# Connectors.net
KiCad netlist of a schematic drawn in Altium Designer
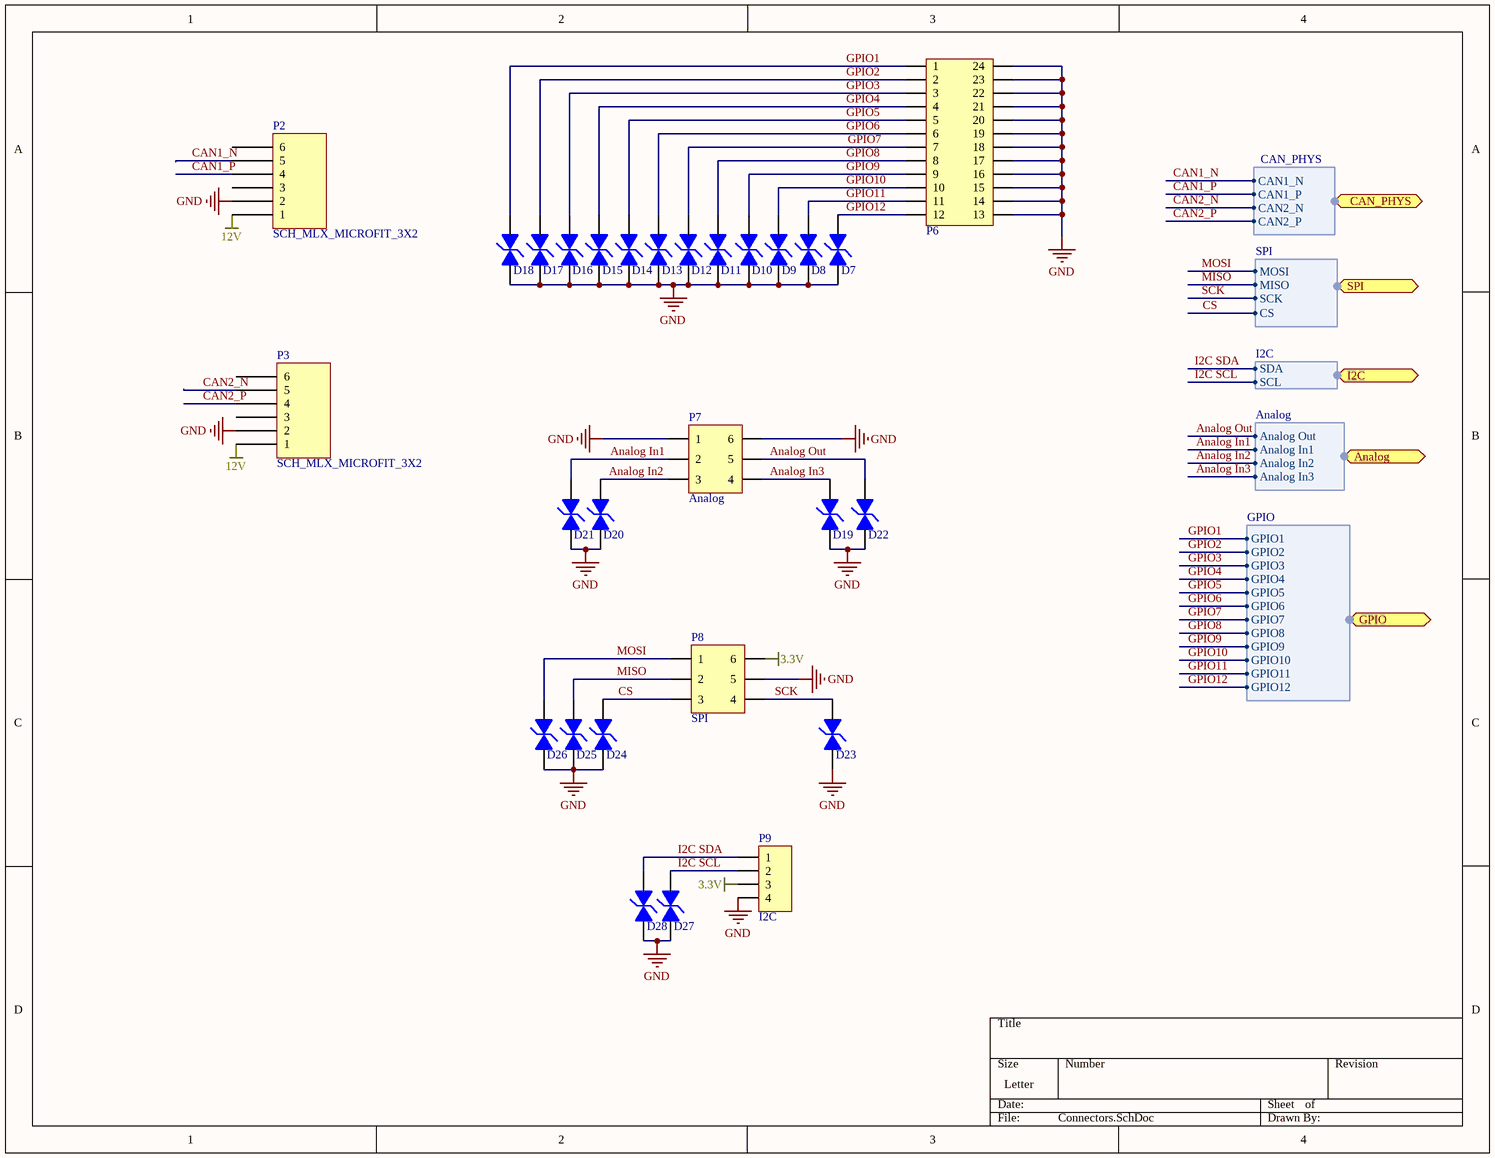
[diagram p0: Connectors.SchDoc]

(export (version "E")
  (design (tool "Eeschema 10.0.6"))
  (components
    (comp (ref "D7")
      (value "TVS Diode")
      (footprint "TVS Diode")
      (fields (field (name "MANUFACTURER") "Bourns"))
      (libsource (lib "TVS Diode") (part "TVS Diode"))
    )
    (comp (ref "D8")
      (value "TVS Diode")
      (footprint "TVS Diode")
      (fields (field (name "MANUFACTURER") "Bourns"))
      (libsource (lib "TVS Diode") (part "TVS Diode"))
    )
    (comp (ref "D9")
      (value "TVS Diode")
      (footprint "TVS Diode")
      (fields (field (name "MANUFACTURER") "Bourns"))
      (libsource (lib "TVS Diode") (part "TVS Diode"))
    )
    (comp (ref "D10")
      (value "TVS Diode")
      (footprint "TVS Diode")
      (fields (field (name "MANUFACTURER") "Bourns"))
      (libsource (lib "TVS Diode") (part "TVS Diode"))
    )
    (comp (ref "D11")
      (value "TVS Diode")
      (footprint "TVS Diode")
      (fields (field (name "MANUFACTURER") "Bourns"))
      (libsource (lib "TVS Diode") (part "TVS Diode"))
    )
    (comp (ref "D12")
      (value "TVS Diode")
      (footprint "TVS Diode")
      (fields (field (name "MANUFACTURER") "Bourns"))
      (libsource (lib "TVS Diode") (part "TVS Diode"))
    )
    (comp (ref "D13")
      (value "TVS Diode")
      (footprint "TVS Diode")
      (fields (field (name "MANUFACTURER") "Bourns"))
      (libsource (lib "TVS Diode") (part "TVS Diode"))
    )
    (comp (ref "D14")
      (value "TVS Diode")
      (footprint "TVS Diode")
      (fields (field (name "MANUFACTURER") "Bourns"))
      (libsource (lib "TVS Diode") (part "TVS Diode"))
    )
    (comp (ref "D15")
      (value "TVS Diode")
      (footprint "TVS Diode")
      (fields (field (name "MANUFACTURER") "Bourns"))
      (libsource (lib "TVS Diode") (part "TVS Diode"))
    )
    (comp (ref "D16")
      (value "TVS Diode")
      (footprint "TVS Diode")
      (fields (field (name "MANUFACTURER") "Bourns"))
      (libsource (lib "TVS Diode") (part "TVS Diode"))
    )
    (comp (ref "D17")
      (value "TVS Diode")
      (footprint "TVS Diode")
      (fields (field (name "MANUFACTURER") "Bourns"))
      (libsource (lib "TVS Diode") (part "TVS Diode"))
    )
    (comp (ref "D18")
      (value "TVS Diode")
      (footprint "TVS Diode")
      (fields (field (name "MANUFACTURER") "Bourns"))
      (libsource (lib "TVS Diode") (part "TVS Diode"))
    )
    (comp (ref "D19")
      (value "TVS Diode")
      (footprint "TVS Diode")
      (fields (field (name "MANUFACTURER") "Bourns"))
      (libsource (lib "TVS Diode") (part "TVS Diode"))
    )
    (comp (ref "D20")
      (value "TVS Diode")
      (footprint "TVS Diode")
      (fields (field (name "MANUFACTURER") "Bourns"))
      (libsource (lib "TVS Diode") (part "TVS Diode"))
    )
    (comp (ref "D21")
      (value "TVS Diode")
      (footprint "TVS Diode")
      (fields (field (name "MANUFACTURER") "Bourns"))
      (libsource (lib "TVS Diode") (part "TVS Diode"))
    )
    (comp (ref "D22")
      (value "TVS Diode")
      (footprint "TVS Diode")
      (fields (field (name "MANUFACTURER") "Bourns"))
      (libsource (lib "TVS Diode") (part "TVS Diode"))
    )
    (comp (ref "D23")
      (value "TVS Diode")
      (footprint "TVS Diode")
      (fields (field (name "MANUFACTURER") "Bourns"))
      (libsource (lib "TVS Diode") (part "TVS Diode"))
    )
    (comp (ref "D24")
      (value "TVS Diode")
      (footprint "TVS Diode")
      (fields (field (name "MANUFACTURER") "Bourns"))
      (libsource (lib "TVS Diode") (part "TVS Diode"))
    )
    (comp (ref "D25")
      (value "TVS Diode")
      (footprint "TVS Diode")
      (fields (field (name "MANUFACTURER") "Bourns"))
      (libsource (lib "TVS Diode") (part "TVS Diode"))
    )
    (comp (ref "D26")
      (value "TVS Diode")
      (footprint "TVS Diode")
      (fields (field (name "MANUFACTURER") "Bourns"))
      (libsource (lib "TVS Diode") (part "TVS Diode"))
    )
    (comp (ref "D27")
      (value "TVS Diode")
      (footprint "TVS Diode")
      (fields (field (name "MANUFACTURER") "Bourns"))
      (libsource (lib "TVS Diode") (part "TVS Diode"))
    )
    (comp (ref "D28")
      (value "TVS Diode")
      (footprint "TVS Diode")
      (fields (field (name "MANUFACTURER") "Bourns"))
      (libsource (lib "TVS Diode") (part "TVS Diode"))
    )
    (comp (ref "P2")
      (value "SCH_MLX_MICROFIT_3X2")
      (footprint "Molex Microfit 3.0 3x2:PCB_MLX_MICROFIT_3X2")
      (libsource (lib "Molex Microfit 3.0 3x2") (part "SCH_MLX_MICROFIT_3X2"))
    )
    (comp (ref "P3")
      (value "SCH_MLX_MICROFIT_3X2")
      (footprint "Molex Microfit 3.0 3x2:PCB_MLX_MICROFIT_3X2")
      (libsource (lib "Molex Microfit 3.0 3x2") (part "SCH_MLX_MICROFIT_3X2"))
    )
    (comp (ref "P6")
      (value "24-Pin Vertical Header")
      (footprint "24-Pin Vertical Header")
      (fields (field (name "MANUFACTURER") "Sullins"))
      (libsource (lib "24 Pin 100 mil Vertical Header - Through Hole") (part "24-Pin Vertical Header"))
    )
    (comp (ref "P7")
      (value "Analog")
      (footprint "6-Pin Vertical Header")
      (fields (field (name "MANUFACTURER") "Sullins"))
      (libsource (lib "6 Pin 100 mil Vertical Header - Through Hole") (part "6-Pin Vertical Header"))
    )
    (comp (ref "P8")
      (value "SPI")
      (footprint "6-Pin Vertical Header")
      (fields (field (name "MANUFACTURER") "Sullins"))
      (libsource (lib "6 Pin 100 mil Vertical Header - Through Hole") (part "6-Pin Vertical Header"))
    )
    (comp (ref "P9")
      (value "I2C")
      (footprint "4-Pin Vertical Header")
      (fields (field (name "MANUFACTURER") "Sullins"))
      (libsource (lib "4 Pin 100 mil Vertical Header - Through Hole") (part "4-Pin Vertical Header"))
    )
  )
  (nets
    (net (code "6") (name "/Analog In1") (class "Default")
      (node (ref "D21") (pin "1") (pintype "passive"))
      (node (ref "P7") (pin "2") (pinfunction "2_2") (pintype "passive"))
    )
    (net (code "7") (name "/Analog In2") (class "Default")
      (node (ref "D20") (pin "1") (pintype "passive"))
      (node (ref "P7") (pin "3") (pinfunction "3_3") (pintype "passive"))
    )
    (net (code "8") (name "/Analog In3") (class "Default")
      (node (ref "D19") (pin "1") (pintype "passive"))
      (node (ref "P7") (pin "4") (pinfunction "4_4") (pintype "passive"))
    )
    (net (code "9") (name "/Analog Out") (class "Default")
      (node (ref "D22") (pin "1") (pintype "passive"))
      (node (ref "P7") (pin "5") (pinfunction "5_5") (pintype "passive"))
    )
    (net (code "10") (name "/CAN1_N") (class "Default")
      (node (ref "P2") (pin "5") (pinfunction "5_5") (pintype "passive"))
    )
    (net (code "11") (name "/CAN1_P") (class "Default")
      (node (ref "P2") (pin "4") (pinfunction "4_4") (pintype "passive"))
    )
    (net (code "12") (name "/CAN2_N") (class "Default")
      (node (ref "P3") (pin "5") (pinfunction "5_5") (pintype "passive"))
    )
    (net (code "13") (name "/CAN2_P") (class "Default")
      (node (ref "P3") (pin "4") (pinfunction "4_4") (pintype "passive"))
    )
    (net (code "14") (name "/CS") (class "Default")
      (node (ref "D24") (pin "1") (pintype "passive"))
      (node (ref "P8") (pin "3") (pinfunction "3_3") (pintype "passive"))
    )
    (net (code "15") (name "/GPIO1") (class "Default")
      (node (ref "D18") (pin "1") (pintype "passive"))
      (node (ref "P6") (pin "1") (pinfunction "1_1") (pintype "passive"))
    )
    (net (code "16") (name "/GPIO2") (class "Default")
      (node (ref "D17") (pin "1") (pintype "passive"))
      (node (ref "P6") (pin "2") (pinfunction "2_2") (pintype "passive"))
    )
    (net (code "17") (name "/GPIO3") (class "Default")
      (node (ref "D16") (pin "1") (pintype "passive"))
      (node (ref "P6") (pin "3") (pinfunction "3_3") (pintype "passive"))
    )
    (net (code "18") (name "/GPIO4") (class "Default")
      (node (ref "D15") (pin "1") (pintype "passive"))
      (node (ref "P6") (pin "4") (pinfunction "4_4") (pintype "passive"))
    )
    (net (code "19") (name "/GPIO5") (class "Default")
      (node (ref "D14") (pin "1") (pintype "passive"))
      (node (ref "P6") (pin "5") (pinfunction "5_5") (pintype "passive"))
    )
    (net (code "20") (name "/GPIO6") (class "Default")
      (node (ref "D13") (pin "1") (pintype "passive"))
      (node (ref "P6") (pin "6") (pinfunction "6_6") (pintype "passive"))
    )
    (net (code "21") (name "/GPIO7") (class "Default")
      (node (ref "D12") (pin "1") (pintype "passive"))
      (node (ref "P6") (pin "7") (pinfunction "7_7") (pintype "passive"))
    )
    (net (code "22") (name "/GPIO8") (class "Default")
      (node (ref "D11") (pin "1") (pintype "passive"))
      (node (ref "P6") (pin "8") (pinfunction "8_8") (pintype "passive"))
    )
    (net (code "23") (name "/GPIO9") (class "Default")
      (node (ref "D10") (pin "1") (pintype "passive"))
      (node (ref "P6") (pin "9") (pinfunction "9_9") (pintype "passive"))
    )
    (net (code "24") (name "/GPIO10") (class "Default")
      (node (ref "D9") (pin "1") (pintype "passive"))
      (node (ref "P6") (pin "10") (pinfunction "10_10") (pintype "passive"))
    )
    (net (code "25") (name "/GPIO11") (class "Default")
      (node (ref "D8") (pin "1") (pintype "passive"))
      (node (ref "P6") (pin "11") (pinfunction "11_11") (pintype "passive"))
    )
    (net (code "26") (name "/GPIO12") (class "Default")
      (node (ref "D7") (pin "1") (pintype "passive"))
      (node (ref "P6") (pin "12") (pinfunction "12_12") (pintype "passive"))
    )
    (net (code "27") (name "/I2C SCL") (class "Default")
      (node (ref "D27") (pin "1") (pintype "passive"))
      (node (ref "P9") (pin "2") (pinfunction "2_2") (pintype "passive"))
    )
    (net (code "28") (name "/I2C SDA") (class "Default")
      (node (ref "D28") (pin "1") (pintype "passive"))
      (node (ref "P9") (pin "1") (pinfunction "1_1") (pintype "passive"))
    )
    (net (code "29") (name "/MISO") (class "Default")
      (node (ref "D25") (pin "1") (pintype "passive"))
      (node (ref "P8") (pin "2") (pinfunction "2_2") (pintype "passive"))
    )
    (net (code "30") (name "/MOSI") (class "Default")
      (node (ref "D26") (pin "1") (pintype "passive"))
      (node (ref "P8") (pin "1") (pinfunction "1_1") (pintype "passive"))
    )
    (net (code "31") (name "/SCK") (class "Default")
      (node (ref "D23") (pin "1") (pintype "passive"))
      (node (ref "P8") (pin "4") (pinfunction "4_4") (pintype "passive"))
    )
    (net (code "37") (name "3.3V") (class "Default")
      (node (ref "P8") (pin "6") (pinfunction "6_6") (pintype "passive"))
      (node (ref "P9") (pin "3") (pinfunction "3_3") (pintype "passive"))
    )
    (net (code "38") (name "12V") (class "Default")
      (node (ref "P2") (pin "1") (pinfunction "1_1") (pintype "passive"))
      (node (ref "P3") (pin "1") (pinfunction "1_1") (pintype "passive"))
    )
    (net (code "39") (name "GND") (class "Default")
      (node (ref "D10") (pin "2") (pintype "passive"))
      (node (ref "D11") (pin "2") (pintype "passive"))
      (node (ref "D12") (pin "2") (pintype "passive"))
      (node (ref "D13") (pin "2") (pintype "passive"))
      (node (ref "D14") (pin "2") (pintype "passive"))
      (node (ref "D15") (pin "2") (pintype "passive"))
      (node (ref "D16") (pin "2") (pintype "passive"))
      (node (ref "D17") (pin "2") (pintype "passive"))
      (node (ref "D18") (pin "2") (pintype "passive"))
      (node (ref "D19") (pin "2") (pintype "passive"))
      (node (ref "D20") (pin "2") (pintype "passive"))
      (node (ref "D21") (pin "2") (pintype "passive"))
      (node (ref "D22") (pin "2") (pintype "passive"))
      (node (ref "D23") (pin "2") (pintype "passive"))
      (node (ref "D24") (pin "2") (pintype "passive"))
      (node (ref "D25") (pin "2") (pintype "passive"))
      (node (ref "D26") (pin "2") (pintype "passive"))
      (node (ref "D27") (pin "2") (pintype "passive"))
      (node (ref "D28") (pin "2") (pintype "passive"))
      (node (ref "D7") (pin "2") (pintype "passive"))
      (node (ref "D8") (pin "2") (pintype "passive"))
      (node (ref "D9") (pin "2") (pintype "passive"))
      (node (ref "P2") (pin "2") (pinfunction "2_2") (pintype "passive"))
      (node (ref "P3") (pin "2") (pinfunction "2_2") (pintype "passive"))
      (node (ref "P6") (pin "13") (pinfunction "13_13") (pintype "passive"))
      (node (ref "P6") (pin "14") (pinfunction "14_14") (pintype "passive"))
      (node (ref "P6") (pin "15") (pinfunction "15_15") (pintype "passive"))
      (node (ref "P6") (pin "16") (pinfunction "16_16") (pintype "passive"))
      (node (ref "P6") (pin "17") (pinfunction "17_17") (pintype "passive"))
      (node (ref "P6") (pin "18") (pinfunction "18_18") (pintype "passive"))
      (node (ref "P6") (pin "19") (pinfunction "19_19") (pintype "passive"))
      (node (ref "P6") (pin "20") (pinfunction "20_20") (pintype "passive"))
      (node (ref "P6") (pin "21") (pinfunction "21_21") (pintype "passive"))
      (node (ref "P6") (pin "22") (pinfunction "22_22") (pintype "passive"))
      (node (ref "P6") (pin "23") (pinfunction "23_23") (pintype "passive"))
      (node (ref "P6") (pin "24") (pinfunction "24_24") (pintype "passive"))
      (node (ref "P7") (pin "1") (pinfunction "1_1") (pintype "passive"))
      (node (ref "P7") (pin "6") (pinfunction "6_6") (pintype "passive"))
      (node (ref "P8") (pin "5") (pinfunction "5_5") (pintype "passive"))
      (node (ref "P9") (pin "4") (pinfunction "4_4") (pintype "passive"))
    )
    (net (code "40") (name "unconnected-(P2-Pad3)") (class "Default")
      (node (ref "P2") (pin "3") (pinfunction "3_3") (pintype "passive"))
    )
    (net (code "41") (name "unconnected-(P2-Pad6)") (class "Default")
      (node (ref "P2") (pin "6") (pinfunction "6_6") (pintype "passive"))
    )
    (net (code "42") (name "unconnected-(P3-Pad3)") (class "Default")
      (node (ref "P3") (pin "3") (pinfunction "3_3") (pintype "passive"))
    )
    (net (code "43") (name "unconnected-(P3-Pad6)") (class "Default")
      (node (ref "P3") (pin "6") (pinfunction "6_6") (pintype "passive"))
    )
  )
)
